# brick_3pin_led_mini.net
KiCad netlist of a schematic drawn in EAGLE
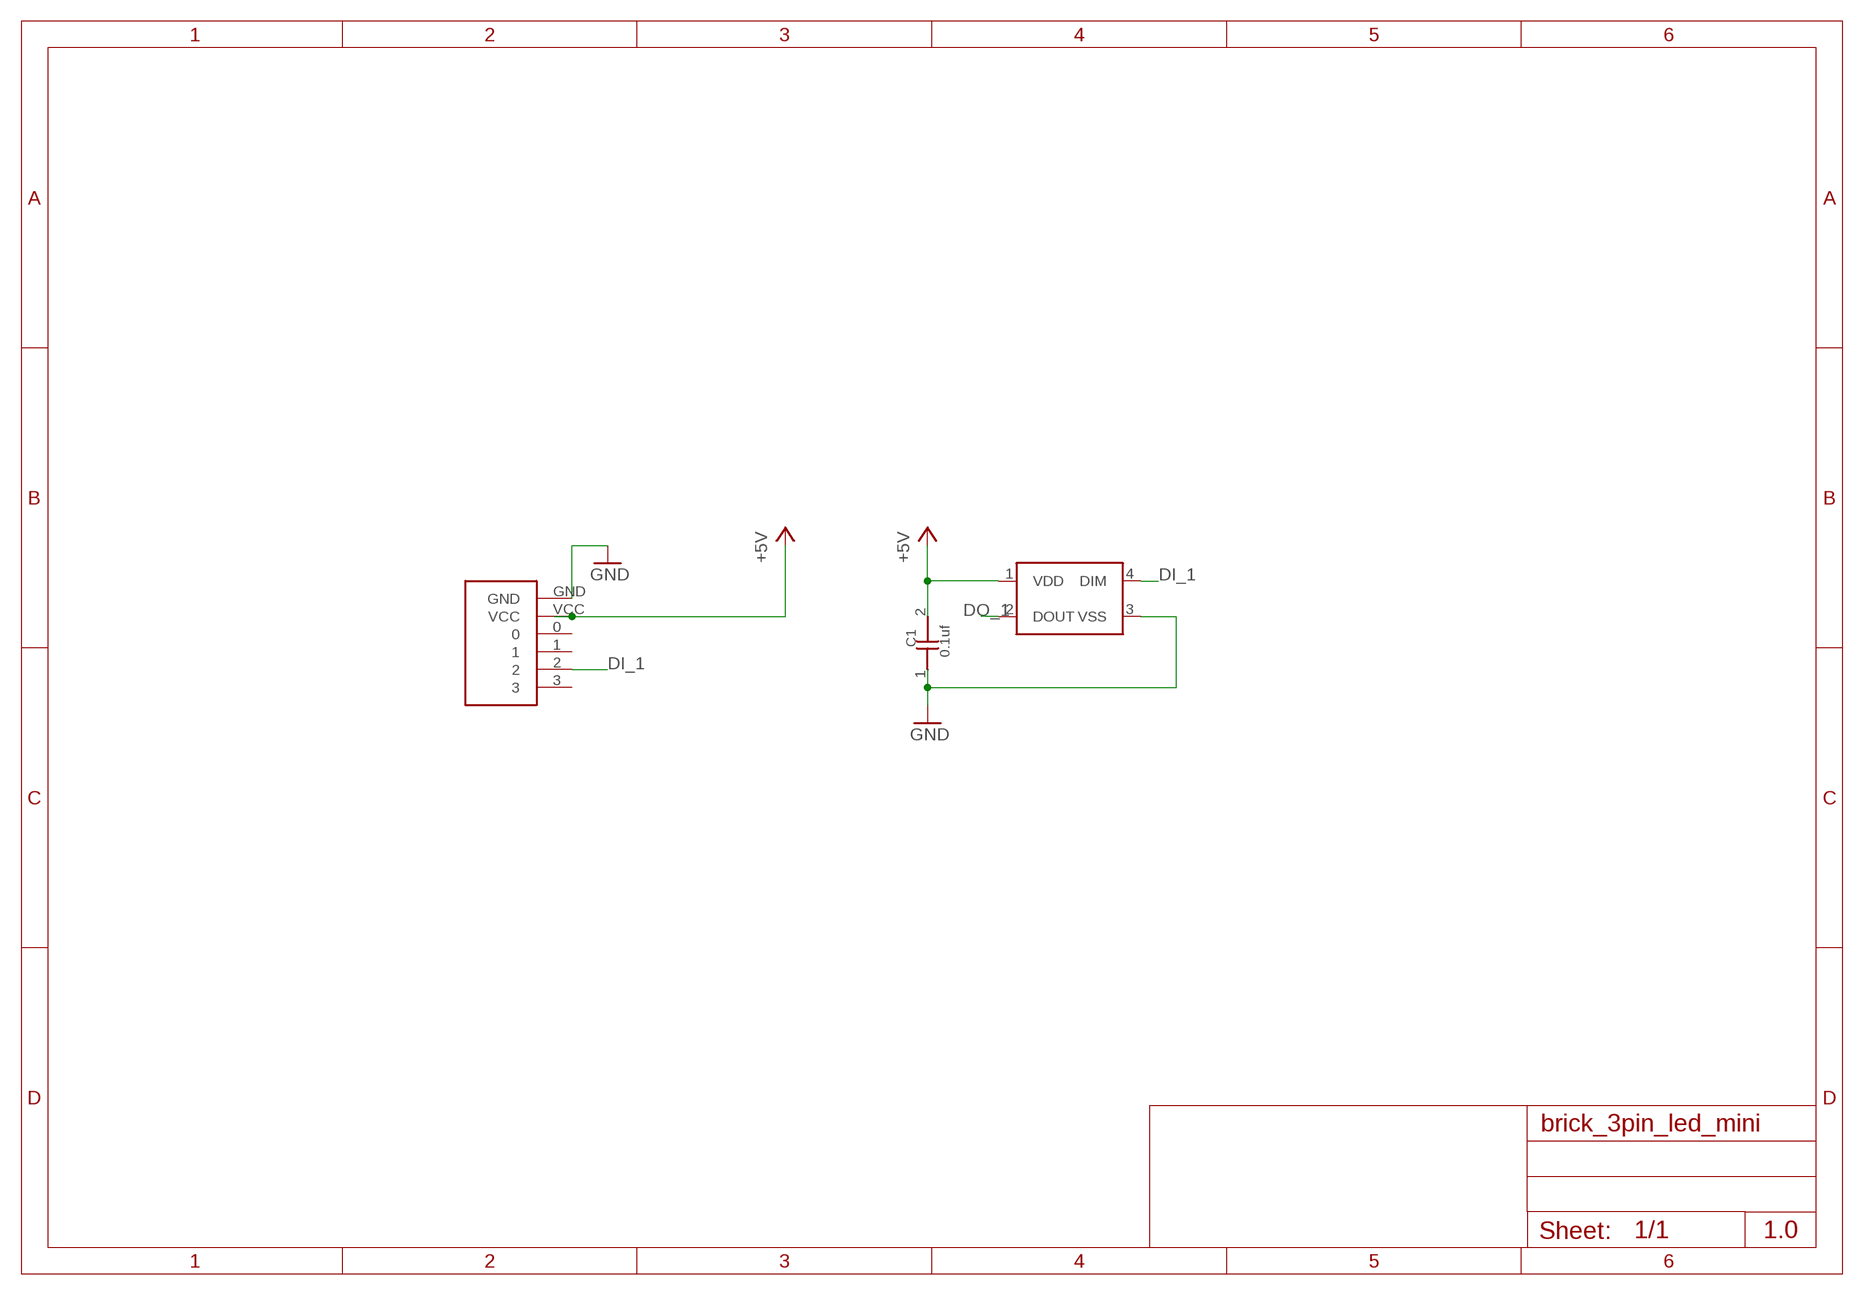
[diagram p0: schematic, sheet 1]

(export (version "E")
  (design (tool "Eeschema 10.0.6"))
  (components
    (comp (ref "C1")
      (value "0.1uf")
      (footprint "eagle-import:0603")
      (libsource (lib "eagle-import") (part "CAPACITOR0603"))
    )
    (comp (ref "LED1")
      (value "WS2818B")
      (footprint "eagle-import:WS2818B")
      (libsource (lib "eagle-import") (part "WS2818B"))
    )
    (comp (ref "U$2")
      (value "FABO-NANO")
      (footprint "eagle-import:FABO-NANO")
      (libsource (lib "eagle-import") (part "FABO-NANO"))
    )
  )
  (nets
    (net (code "1") (name "+5V") (class "Default")
      (node (ref "C1") (pin "2") (pinfunction "2_2") (pintype "passive"))
      (node (ref "LED1") (pin "1") (pinfunction "VDD_1") (pintype "bidirectional"))
      (node (ref "U$2") (pin "VCC") (pinfunction "VCC_VCC") (pintype "bidirectional"))
    )
    (net (code "2") (name "/DI_1") (class "Default")
      (node (ref "LED1") (pin "4") (pinfunction "DIM_4") (pintype "bidirectional"))
      (node (ref "U$2") (pin "2") (pinfunction "2_2") (pintype "bidirectional"))
    )
    (net (code "3") (name "/DO_1") (class "Default")
      (node (ref "LED1") (pin "2") (pinfunction "DOUT_2") (pintype "bidirectional"))
    )
    (net (code "4") (name "GND") (class "Default")
      (node (ref "C1") (pin "1") (pinfunction "1_1") (pintype "passive"))
      (node (ref "LED1") (pin "3") (pinfunction "VSS_3") (pintype "bidirectional"))
      (node (ref "U$2") (pin "GND") (pinfunction "GND_GND") (pintype "bidirectional"))
    )
    (net (code "5") (name "unconnected-(U$2-Pad0)") (class "Default")
      (node (ref "U$2") (pin "0") (pinfunction "0_0") (pintype "bidirectional"))
    )
    (net (code "6") (name "unconnected-(U$2-Pad1)") (class "Default")
      (node (ref "U$2") (pin "1") (pinfunction "1_1") (pintype "bidirectional"))
    )
    (net (code "7") (name "unconnected-(U$2-Pad3)") (class "Default")
      (node (ref "U$2") (pin "3") (pinfunction "3_3") (pintype "bidirectional"))
    )
  )
)
